# Sheet1.net
KiCad netlist of a schematic drawn in Altium Designer
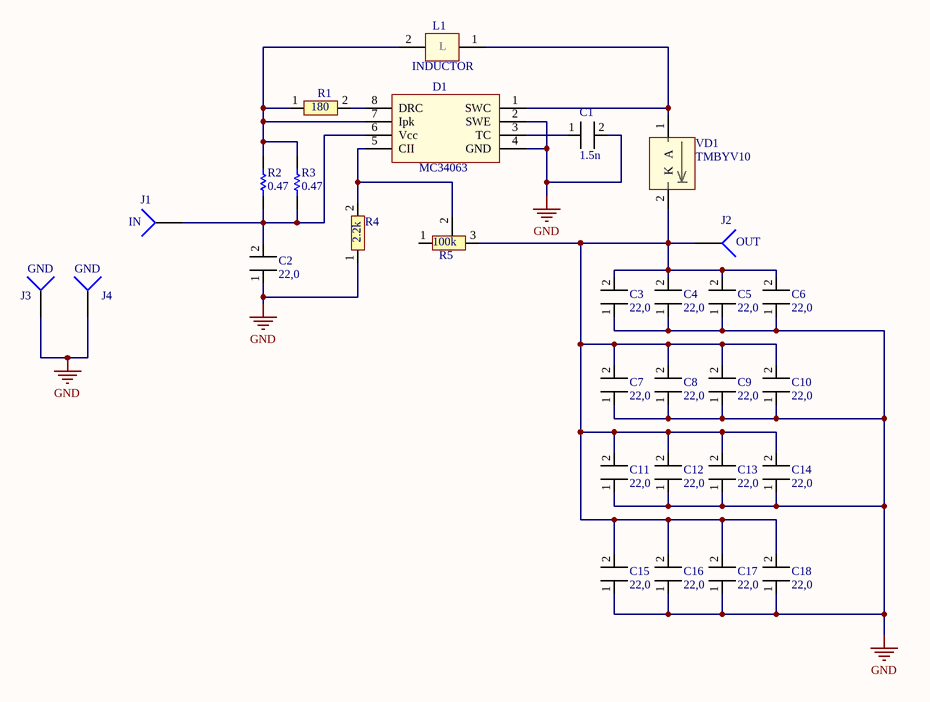
[diagram p0: Sheet1.SchDoc]

(export (version "E")
  (design (tool "Eeschema 10.0.6"))
  (components
    (comp (ref "C1") (value "1.5n") (footprint "CAP_SMALL") (libsource (lib "Schlib") (part "CAP_SMALL")))
    (comp (ref "C2") (value "22,0") (footprint "Cap_BIG") (libsource (lib "Schlib") (part "CAP_BIG")))
    (comp (ref "C3") (value "22,0") (footprint "MHDR1X2") (libsource (lib "Schlib") (part "CAP_BIG")))
    (comp (ref "C4") (value "22,0") (footprint "MHDR1X2") (libsource (lib "Schlib") (part "CAP_BIG")))
    (comp (ref "C5") (value "22,0") (footprint "MHDR1X2") (libsource (lib "Schlib") (part "CAP_BIG")))
    (comp (ref "C6") (value "22,0") (footprint "MHDR1X2") (libsource (lib "Schlib") (part "CAP_BIG")))
    (comp (ref "C7") (value "22,0") (footprint "MHDR1X2") (libsource (lib "Schlib") (part "CAP_BIG")))
    (comp (ref "C8") (value "22,0") (footprint "MHDR1X2") (libsource (lib "Schlib") (part "CAP_BIG")))
    (comp (ref "C9") (value "22,0") (footprint "MHDR1X2") (libsource (lib "Schlib") (part "CAP_BIG")))
    (comp (ref "C10") (value "22,0") (footprint "MHDR1X2") (libsource (lib "Schlib") (part "CAP_BIG")))
    (comp (ref "C11") (value "22,0") (footprint "MHDR1X2") (libsource (lib "Schlib") (part "CAP_BIG")))
    (comp (ref "C12") (value "22,0") (footprint "MHDR1X2") (libsource (lib "Schlib") (part "CAP_BIG")))
    (comp (ref "C13") (value "22,0") (footprint "MHDR1X2") (libsource (lib "Schlib") (part "CAP_BIG")))
    (comp (ref "C14") (value "22,0") (footprint "MHDR1X2") (libsource (lib "Schlib") (part "CAP_BIG")))
    (comp (ref "C15") (value "22,0") (footprint "MHDR1X2") (libsource (lib "Schlib") (part "CAP_BIG")))
    (comp (ref "C16") (value "22,0") (footprint "MHDR1X2") (libsource (lib "Schlib") (part "CAP_BIG")))
    (comp (ref "C17") (value "22,0") (footprint "MHDR1X2") (libsource (lib "Schlib") (part "CAP_BIG")))
    (comp (ref "C18") (value "22,0") (footprint "MHDR1X2") (libsource (lib "Schlib") (part "CAP_BIG")))
    (comp (ref "D1")
      (value "MC34063")
      (footprint "SOIC127P600X175-8N")
      (libsource (lib "Schlib") (part "MC34063A/E"))
    )
    (comp (ref "J1")
      (value "IN")
      (footprint "PIN1")
      (description "Socket")
      (fields (field (name "PUBLISHER") "Altium Limited"))
      (libsource (lib "Miscellaneous Connectors") (part "Socket"))
    )
    (comp (ref "J2")
      (value "OUT")
      (footprint "PIN1")
      (description "Socket")
      (fields (field (name "PUBLISHER") "Altium Limited"))
      (libsource (lib "Miscellaneous Connectors") (part "Socket"))
    )
    (comp (ref "J3")
      (value "GND")
      (footprint "PIN1")
      (description "Socket")
      (fields (field (name "PUBLISHER") "Altium Limited"))
      (libsource (lib "Miscellaneous Connectors") (part "Socket"))
    )
    (comp (ref "J4")
      (value "GND")
      (footprint "PIN1")
      (description "Socket")
      (fields (field (name "PUBLISHER") "Altium Limited"))
      (libsource (lib "Miscellaneous Connectors") (part "Socket"))
    )
    (comp (ref "L1") (value "INDUCTOR") (footprint "1812") (libsource (lib "Schlib") (part "INDUCTOR")))
    (comp (ref "R1") (value "180") (footprint "RES") (libsource (lib "Schlib") (part "RES")))
    (comp (ref "R2")
      (value "0.47")
      (footprint "AXIAL-0.3")
      (description "Resistor")
      (fields (field (name "PUBLISHER") "Altium Limited"))
      (libsource (lib "Miscellaneous Devices") (part "Res1"))
    )
    (comp (ref "R3")
      (value "0.47")
      (footprint "AXIAL-0.3")
      (description "Resistor")
      (fields (field (name "PUBLISHER") "Altium Limited"))
      (libsource (lib "Miscellaneous Devices") (part "Res1"))
    )
    (comp (ref "R4") (value "2.2k") (footprint "RES") (libsource (lib "") (part "RES_1")))
    (comp (ref "R5")
      (value "100k")
      (footprint "PODSTR_RES_1")
      (libsource (lib "Schlib") (part "RES_PODSTR_1"))
    )
    (comp (ref "VD1")
      (value "TMBYV10")
      (footprint "TMBYV10-60")
      (libsource (lib "Schlib") (part "TMBYV10-60"))
    )
  )
  (nets
    (net (code "1") (name "GND") (class "Default")
      (node (ref "C1") (pin "2") (pinfunction "2_2") (pintype "passive"))
      (node (ref "C10") (pin "1") (pinfunction "1_1") (pintype "passive"))
      (node (ref "C11") (pin "1") (pinfunction "1_1") (pintype "passive"))
      (node (ref "C12") (pin "1") (pinfunction "1_1") (pintype "passive"))
      (node (ref "C13") (pin "1") (pinfunction "1_1") (pintype "passive"))
      (node (ref "C14") (pin "1") (pinfunction "1_1") (pintype "passive"))
      (node (ref "C15") (pin "1") (pinfunction "1_1") (pintype "passive"))
      (node (ref "C16") (pin "1") (pinfunction "1_1") (pintype "passive"))
      (node (ref "C17") (pin "1") (pinfunction "1_1") (pintype "passive"))
      (node (ref "C18") (pin "1") (pinfunction "1_1") (pintype "passive"))
      (node (ref "C2") (pin "1") (pinfunction "1_1") (pintype "passive"))
      (node (ref "C3") (pin "1") (pinfunction "1_1") (pintype "passive"))
      (node (ref "C4") (pin "1") (pinfunction "1_1") (pintype "passive"))
      (node (ref "C5") (pin "1") (pinfunction "1_1") (pintype "passive"))
      (node (ref "C6") (pin "1") (pinfunction "1_1") (pintype "passive"))
      (node (ref "C7") (pin "1") (pinfunction "1_1") (pintype "passive"))
      (node (ref "C8") (pin "1") (pinfunction "1_1") (pintype "passive"))
      (node (ref "C9") (pin "1") (pinfunction "1_1") (pintype "passive"))
      (node (ref "D1") (pin "2") (pinfunction "SWE_2") (pintype "passive"))
      (node (ref "D1") (pin "4") (pinfunction "GND_4") (pintype "passive"))
      (node (ref "J3") (pin "1") (pinfunction "1_1") (pintype "passive"))
      (node (ref "J4") (pin "1") (pinfunction "1_1") (pintype "passive"))
      (node (ref "R4") (pin "1") (pinfunction "1_1") (pintype "passive"))
    )
    (net (code "2") (name "Net-(D1-CII)") (class "Default")
      (node (ref "D1") (pin "5") (pinfunction "CII_5") (pintype "passive"))
      (node (ref "R4") (pin "2") (pinfunction "2_2") (pintype "passive"))
      (node (ref "R5") (pin "2") (pinfunction "2_2") (pintype "passive"))
    )
    (net (code "3") (name "Net-(D1-DRC)") (class "Default")
      (node (ref "D1") (pin "8") (pinfunction "DRC_8") (pintype "passive"))
      (node (ref "R1") (pin "2") (pinfunction "2_2") (pintype "passive"))
    )
    (net (code "4") (name "Net-(D1-Ipk)") (class "Default")
      (node (ref "D1") (pin "7") (pinfunction "Ipk_7") (pintype "passive"))
      (node (ref "L1") (pin "2") (pinfunction "2_2") (pintype "passive"))
      (node (ref "R1") (pin "1") (pinfunction "1_1") (pintype "passive"))
      (node (ref "R2") (pin "2") (pinfunction "2_2") (pintype "passive"))
      (node (ref "R3") (pin "2") (pinfunction "2_2") (pintype "passive"))
    )
    (net (code "5") (name "Net-(D1-SWC)") (class "Default")
      (node (ref "D1") (pin "1") (pinfunction "SWC_1") (pintype "passive"))
      (node (ref "L1") (pin "1") (pinfunction "1_1") (pintype "passive"))
      (node (ref "VD1") (pin "1") (pinfunction "A_1") (pintype "passive"))
    )
    (net (code "6") (name "Net-(D1-TC)") (class "Default")
      (node (ref "C1") (pin "1") (pinfunction "1_1") (pintype "passive"))
      (node (ref "D1") (pin "3") (pinfunction "TC_3") (pintype "passive"))
    )
    (net (code "7") (name "Net-(D1-Vcc)") (class "Default")
      (node (ref "C2") (pin "2") (pinfunction "2_2") (pintype "passive"))
      (node (ref "D1") (pin "6") (pinfunction "Vcc_6") (pintype "passive"))
      (node (ref "J1") (pin "1") (pinfunction "1_1") (pintype "passive"))
      (node (ref "R2") (pin "1") (pinfunction "1_1") (pintype "passive"))
      (node (ref "R3") (pin "1") (pinfunction "1_1") (pintype "passive"))
    )
    (net (code "8") (name "Net-(VD1-K)") (class "Default")
      (node (ref "C10") (pin "2") (pinfunction "2_2") (pintype "passive"))
      (node (ref "C11") (pin "2") (pinfunction "2_2") (pintype "passive"))
      (node (ref "C12") (pin "2") (pinfunction "2_2") (pintype "passive"))
      (node (ref "C13") (pin "2") (pinfunction "2_2") (pintype "passive"))
      (node (ref "C14") (pin "2") (pinfunction "2_2") (pintype "passive"))
      (node (ref "C15") (pin "2") (pinfunction "2_2") (pintype "passive"))
      (node (ref "C16") (pin "2") (pinfunction "2_2") (pintype "passive"))
      (node (ref "C17") (pin "2") (pinfunction "2_2") (pintype "passive"))
      (node (ref "C18") (pin "2") (pinfunction "2_2") (pintype "passive"))
      (node (ref "C3") (pin "2") (pinfunction "2_2") (pintype "passive"))
      (node (ref "C4") (pin "2") (pinfunction "2_2") (pintype "passive"))
      (node (ref "C5") (pin "2") (pinfunction "2_2") (pintype "passive"))
      (node (ref "C6") (pin "2") (pinfunction "2_2") (pintype "passive"))
      (node (ref "C7") (pin "2") (pinfunction "2_2") (pintype "passive"))
      (node (ref "C8") (pin "2") (pinfunction "2_2") (pintype "passive"))
      (node (ref "C9") (pin "2") (pinfunction "2_2") (pintype "passive"))
      (node (ref "J2") (pin "1") (pinfunction "1_1") (pintype "passive"))
      (node (ref "R5") (pin "3") (pinfunction "3_3") (pintype "passive"))
      (node (ref "VD1") (pin "2") (pinfunction "K_2") (pintype "passive"))
    )
    (net (code "9") (name "unconnected-(R5-Pad1)") (class "Default")
      (node (ref "R5") (pin "1") (pinfunction "1_1") (pintype "passive"))
    )
  )
)
